# keypad-input.net
KiCad netlist of a schematic drawn in EAGLE
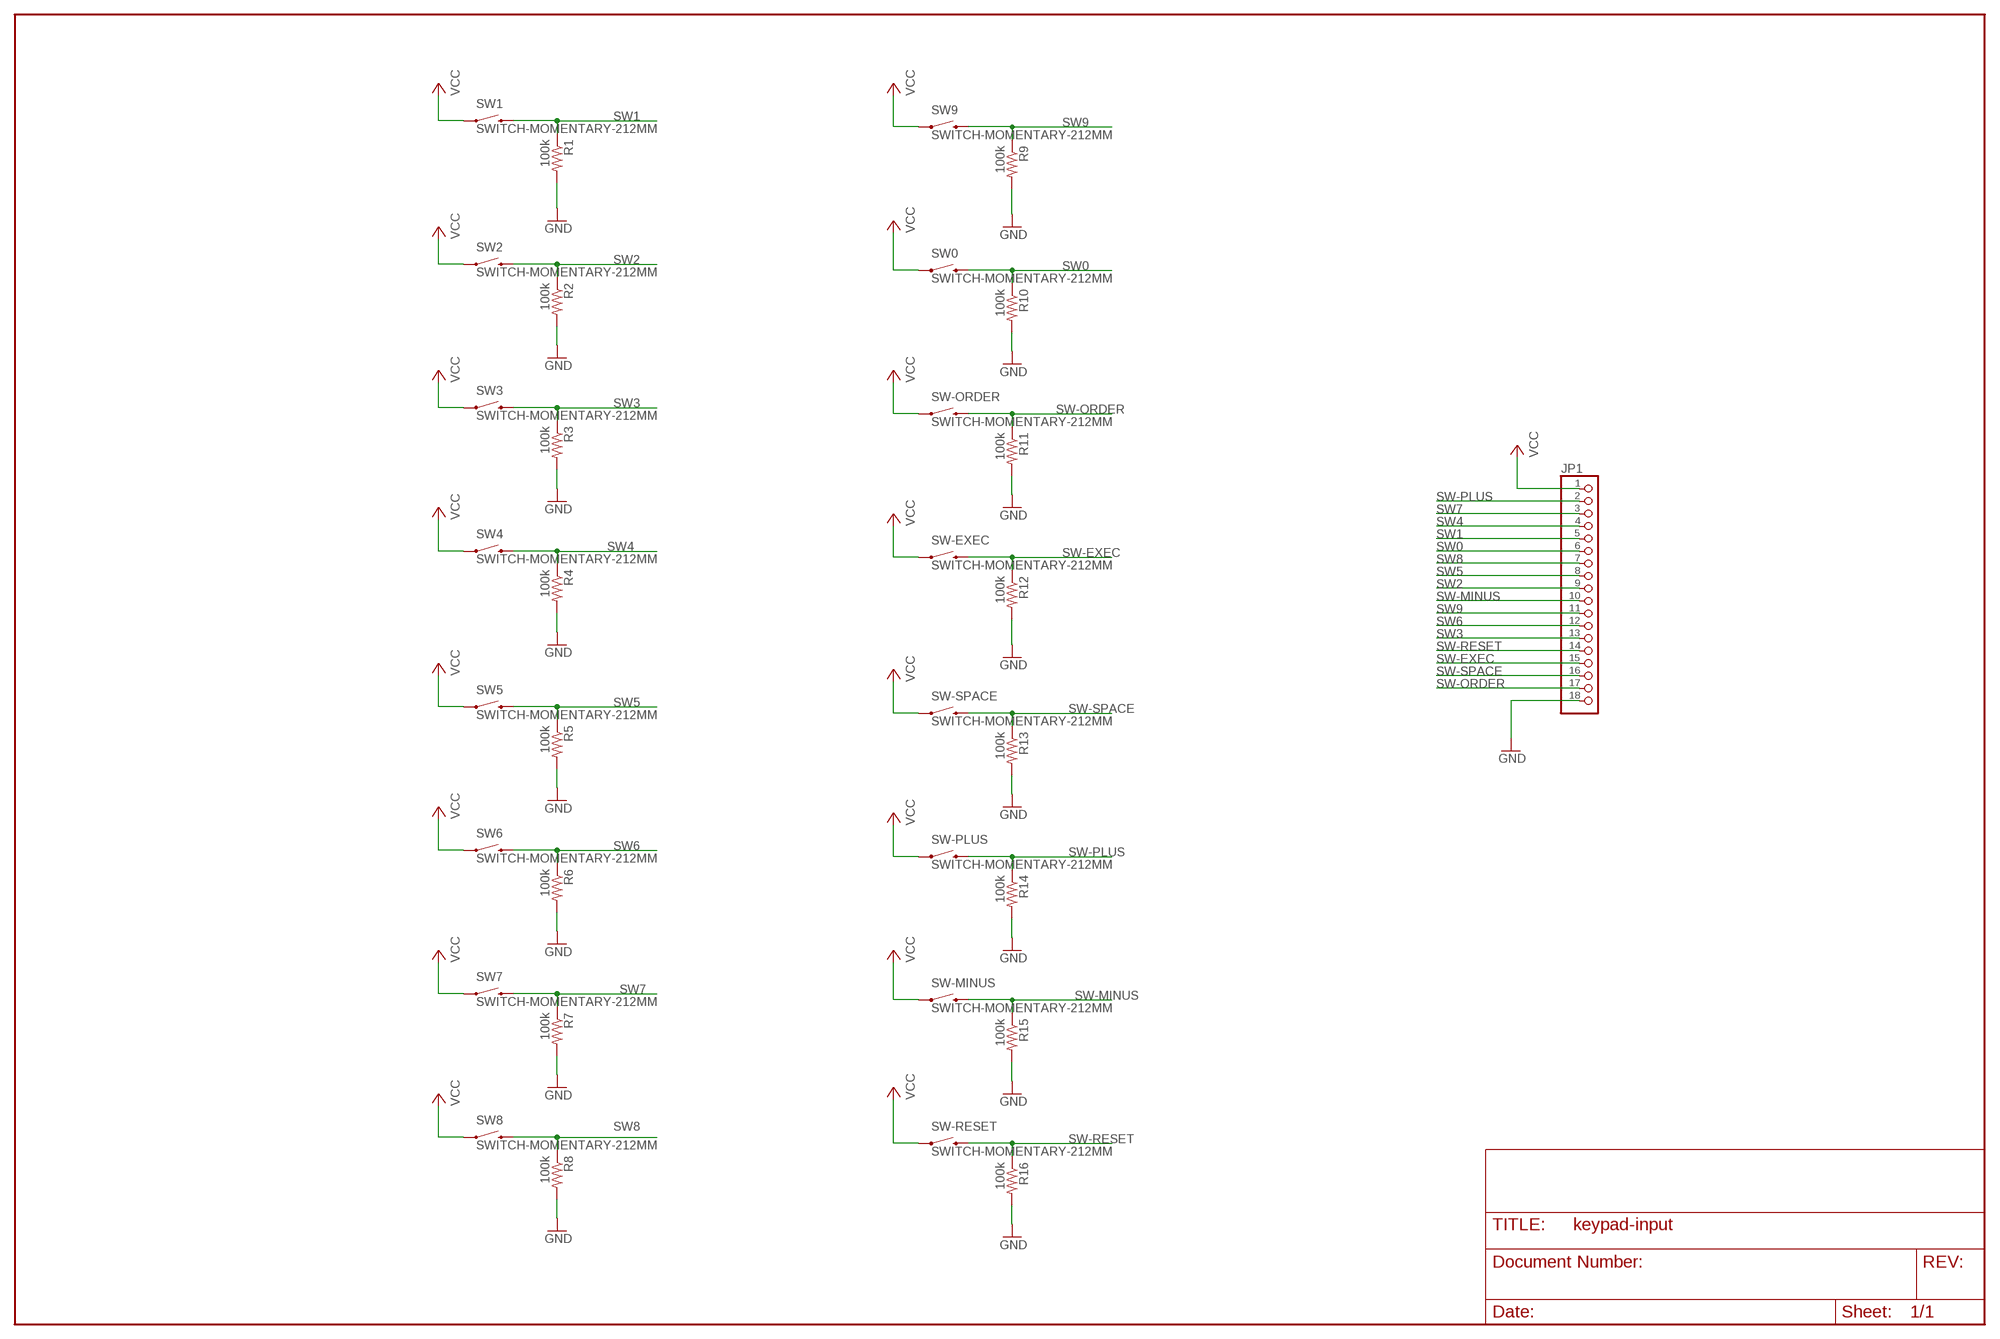
[diagram p0: schematic, sheet 1]

(export (version "E")
  (design (tool "Eeschema 10.0.6"))
  (components
    (comp (ref "JP1")
      (value "PINHD-1X18")
      (footprint "eagle-import:1X18")
      (libsource (lib "eagle-import") (part "PINHD-1X18"))
    )
    (comp (ref "R1")
      (value "100k")
      (footprint "eagle-import:R0805")
      (libsource (lib "eagle-import") (part "R-US_R0805"))
    )
    (comp (ref "R2")
      (value "100k")
      (footprint "eagle-import:R0805")
      (libsource (lib "eagle-import") (part "R-US_R0805"))
    )
    (comp (ref "R3")
      (value "100k")
      (footprint "eagle-import:R0805")
      (libsource (lib "eagle-import") (part "R-US_R0805"))
    )
    (comp (ref "R4")
      (value "100k")
      (footprint "eagle-import:R0805")
      (libsource (lib "eagle-import") (part "R-US_R0805"))
    )
    (comp (ref "R5")
      (value "100k")
      (footprint "eagle-import:R0805")
      (libsource (lib "eagle-import") (part "R-US_R0805"))
    )
    (comp (ref "R6")
      (value "100k")
      (footprint "eagle-import:R0805")
      (libsource (lib "eagle-import") (part "R-US_R0805"))
    )
    (comp (ref "R7")
      (value "100k")
      (footprint "eagle-import:R0805")
      (libsource (lib "eagle-import") (part "R-US_R0805"))
    )
    (comp (ref "R8")
      (value "100k")
      (footprint "eagle-import:R0805")
      (libsource (lib "eagle-import") (part "R-US_R0805"))
    )
    (comp (ref "R9")
      (value "100k")
      (footprint "eagle-import:R0805")
      (libsource (lib "eagle-import") (part "R-US_R0805"))
    )
    (comp (ref "R10")
      (value "100k")
      (footprint "eagle-import:R0805")
      (libsource (lib "eagle-import") (part "R-US_R0805"))
    )
    (comp (ref "R11")
      (value "100k")
      (footprint "eagle-import:R0805")
      (libsource (lib "eagle-import") (part "R-US_R0805"))
    )
    (comp (ref "R12")
      (value "100k")
      (footprint "eagle-import:R0805")
      (libsource (lib "eagle-import") (part "R-US_R0805"))
    )
    (comp (ref "R13")
      (value "100k")
      (footprint "eagle-import:R0805")
      (libsource (lib "eagle-import") (part "R-US_R0805"))
    )
    (comp (ref "R14")
      (value "100k")
      (footprint "eagle-import:R0805")
      (libsource (lib "eagle-import") (part "R-US_R0805"))
    )
    (comp (ref "R15")
      (value "100k")
      (footprint "eagle-import:R0805")
      (libsource (lib "eagle-import") (part "R-US_R0805"))
    )
    (comp (ref "R16")
      (value "100k")
      (footprint "eagle-import:R0805")
      (libsource (lib "eagle-import") (part "R-US_R0805"))
    )
    (comp (ref "SW-EXEC")
      (value "SWITCH-MOMENTARY-212MM")
      (footprint "eagle-import:TACTILE-PTH-12MM")
      (libsource (lib "eagle-import") (part "SWITCH-MOMENTARY-212MM"))
    )
    (comp (ref "SW-MINUS")
      (value "SWITCH-MOMENTARY-212MM")
      (footprint "eagle-import:TACTILE-PTH-12MM")
      (libsource (lib "eagle-import") (part "SWITCH-MOMENTARY-212MM"))
    )
    (comp (ref "SW-ORDER")
      (value "SWITCH-MOMENTARY-212MM")
      (footprint "eagle-import:TACTILE-PTH-12MM")
      (libsource (lib "eagle-import") (part "SWITCH-MOMENTARY-212MM"))
    )
    (comp (ref "SW-PLUS")
      (value "SWITCH-MOMENTARY-212MM")
      (footprint "eagle-import:TACTILE-PTH-12MM")
      (libsource (lib "eagle-import") (part "SWITCH-MOMENTARY-212MM"))
    )
    (comp (ref "SW-RESET")
      (value "SWITCH-MOMENTARY-212MM")
      (footprint "eagle-import:TACTILE-PTH-12MM")
      (libsource (lib "eagle-import") (part "SWITCH-MOMENTARY-212MM"))
    )
    (comp (ref "SW-SPACE")
      (value "SWITCH-MOMENTARY-212MM")
      (footprint "eagle-import:TACTILE-PTH-12MM")
      (libsource (lib "eagle-import") (part "SWITCH-MOMENTARY-212MM"))
    )
    (comp (ref "SW0")
      (value "SWITCH-MOMENTARY-212MM")
      (footprint "eagle-import:TACTILE-PTH-12MM")
      (libsource (lib "eagle-import") (part "SWITCH-MOMENTARY-212MM"))
    )
    (comp (ref "SW1")
      (value "SWITCH-MOMENTARY-212MM")
      (footprint "eagle-import:TACTILE-PTH-12MM")
      (libsource (lib "eagle-import") (part "SWITCH-MOMENTARY-212MM"))
    )
    (comp (ref "SW2")
      (value "SWITCH-MOMENTARY-212MM")
      (footprint "eagle-import:TACTILE-PTH-12MM")
      (libsource (lib "eagle-import") (part "SWITCH-MOMENTARY-212MM"))
    )
    (comp (ref "SW3")
      (value "SWITCH-MOMENTARY-212MM")
      (footprint "eagle-import:TACTILE-PTH-12MM")
      (libsource (lib "eagle-import") (part "SWITCH-MOMENTARY-212MM"))
    )
    (comp (ref "SW4")
      (value "SWITCH-MOMENTARY-212MM")
      (footprint "eagle-import:TACTILE-PTH-12MM")
      (libsource (lib "eagle-import") (part "SWITCH-MOMENTARY-212MM"))
    )
    (comp (ref "SW5")
      (value "SWITCH-MOMENTARY-212MM")
      (footprint "eagle-import:TACTILE-PTH-12MM")
      (libsource (lib "eagle-import") (part "SWITCH-MOMENTARY-212MM"))
    )
    (comp (ref "SW6")
      (value "SWITCH-MOMENTARY-212MM")
      (footprint "eagle-import:TACTILE-PTH-12MM")
      (libsource (lib "eagle-import") (part "SWITCH-MOMENTARY-212MM"))
    )
    (comp (ref "SW7")
      (value "SWITCH-MOMENTARY-212MM")
      (footprint "eagle-import:TACTILE-PTH-12MM")
      (libsource (lib "eagle-import") (part "SWITCH-MOMENTARY-212MM"))
    )
    (comp (ref "SW8")
      (value "SWITCH-MOMENTARY-212MM")
      (footprint "eagle-import:TACTILE-PTH-12MM")
      (libsource (lib "eagle-import") (part "SWITCH-MOMENTARY-212MM"))
    )
    (comp (ref "SW9")
      (value "SWITCH-MOMENTARY-212MM")
      (footprint "eagle-import:TACTILE-PTH-12MM")
      (libsource (lib "eagle-import") (part "SWITCH-MOMENTARY-212MM"))
    )
  )
  (nets
    (net (code "1") (name "/SW-EXEC") (class "Default")
      (node (ref "JP1") (pin "15") (pinfunction "15_15") (pintype "passive"))
      (node (ref "R12") (pin "1") (pinfunction "1_1") (pintype "passive"))
      (node (ref "SW-EXEC") (pin "3") (pinfunction "2_3") (pintype "passive"))
    )
    (net (code "2") (name "/SW-MINUS") (class "Default")
      (node (ref "JP1") (pin "10") (pinfunction "10_10") (pintype "passive"))
      (node (ref "R15") (pin "1") (pinfunction "1_1") (pintype "passive"))
      (node (ref "SW-MINUS") (pin "3") (pinfunction "2_3") (pintype "passive"))
    )
    (net (code "3") (name "/SW-ORDER") (class "Default")
      (node (ref "JP1") (pin "17") (pinfunction "17_17") (pintype "passive"))
      (node (ref "R11") (pin "1") (pinfunction "1_1") (pintype "passive"))
      (node (ref "SW-ORDER") (pin "3") (pinfunction "2_3") (pintype "passive"))
    )
    (net (code "4") (name "/SW-PLUS") (class "Default")
      (node (ref "JP1") (pin "2") (pinfunction "2_2") (pintype "passive"))
      (node (ref "R14") (pin "1") (pinfunction "1_1") (pintype "passive"))
      (node (ref "SW-PLUS") (pin "3") (pinfunction "2_3") (pintype "passive"))
    )
    (net (code "5") (name "/SW-RESET") (class "Default")
      (node (ref "JP1") (pin "14") (pinfunction "14_14") (pintype "passive"))
      (node (ref "R16") (pin "1") (pinfunction "1_1") (pintype "passive"))
      (node (ref "SW-RESET") (pin "3") (pinfunction "2_3") (pintype "passive"))
    )
    (net (code "6") (name "/SW-SPACE") (class "Default")
      (node (ref "JP1") (pin "16") (pinfunction "16_16") (pintype "passive"))
      (node (ref "R13") (pin "1") (pinfunction "1_1") (pintype "passive"))
      (node (ref "SW-SPACE") (pin "3") (pinfunction "2_3") (pintype "passive"))
    )
    (net (code "7") (name "/SW0") (class "Default")
      (node (ref "JP1") (pin "6") (pinfunction "6_6") (pintype "passive"))
      (node (ref "R10") (pin "1") (pinfunction "1_1") (pintype "passive"))
      (node (ref "SW0") (pin "3") (pinfunction "2_3") (pintype "passive"))
    )
    (net (code "8") (name "/SW1") (class "Default")
      (node (ref "JP1") (pin "5") (pinfunction "5_5") (pintype "passive"))
      (node (ref "R1") (pin "1") (pinfunction "1_1") (pintype "passive"))
      (node (ref "SW1") (pin "3") (pinfunction "2_3") (pintype "passive"))
    )
    (net (code "9") (name "/SW2") (class "Default")
      (node (ref "JP1") (pin "9") (pinfunction "9_9") (pintype "passive"))
      (node (ref "R2") (pin "1") (pinfunction "1_1") (pintype "passive"))
      (node (ref "SW2") (pin "3") (pinfunction "2_3") (pintype "passive"))
    )
    (net (code "10") (name "/SW3") (class "Default")
      (node (ref "JP1") (pin "13") (pinfunction "13_13") (pintype "passive"))
      (node (ref "R3") (pin "1") (pinfunction "1_1") (pintype "passive"))
      (node (ref "SW3") (pin "3") (pinfunction "2_3") (pintype "passive"))
    )
    (net (code "11") (name "/SW4") (class "Default")
      (node (ref "JP1") (pin "4") (pinfunction "4_4") (pintype "passive"))
      (node (ref "R4") (pin "1") (pinfunction "1_1") (pintype "passive"))
      (node (ref "SW4") (pin "3") (pinfunction "2_3") (pintype "passive"))
    )
    (net (code "12") (name "/SW5") (class "Default")
      (node (ref "JP1") (pin "8") (pinfunction "8_8") (pintype "passive"))
      (node (ref "R5") (pin "1") (pinfunction "1_1") (pintype "passive"))
      (node (ref "SW5") (pin "3") (pinfunction "2_3") (pintype "passive"))
    )
    (net (code "13") (name "/SW6") (class "Default")
      (node (ref "JP1") (pin "12") (pinfunction "12_12") (pintype "passive"))
      (node (ref "R6") (pin "1") (pinfunction "1_1") (pintype "passive"))
      (node (ref "SW6") (pin "3") (pinfunction "2_3") (pintype "passive"))
    )
    (net (code "14") (name "/SW7") (class "Default")
      (node (ref "JP1") (pin "3") (pinfunction "3_3") (pintype "passive"))
      (node (ref "R7") (pin "1") (pinfunction "1_1") (pintype "passive"))
      (node (ref "SW7") (pin "3") (pinfunction "2_3") (pintype "passive"))
    )
    (net (code "15") (name "/SW8") (class "Default")
      (node (ref "JP1") (pin "7") (pinfunction "7_7") (pintype "passive"))
      (node (ref "R8") (pin "1") (pinfunction "1_1") (pintype "passive"))
      (node (ref "SW8") (pin "3") (pinfunction "2_3") (pintype "passive"))
    )
    (net (code "16") (name "/SW9") (class "Default")
      (node (ref "JP1") (pin "11") (pinfunction "11_11") (pintype "passive"))
      (node (ref "R9") (pin "1") (pinfunction "1_1") (pintype "passive"))
      (node (ref "SW9") (pin "3") (pinfunction "2_3") (pintype "passive"))
    )
    (net (code "17") (name "GND") (class "Default")
      (node (ref "JP1") (pin "18") (pinfunction "18_18") (pintype "passive"))
      (node (ref "R1") (pin "2") (pinfunction "2_2") (pintype "passive"))
      (node (ref "R10") (pin "2") (pinfunction "2_2") (pintype "passive"))
      (node (ref "R11") (pin "2") (pinfunction "2_2") (pintype "passive"))
      (node (ref "R12") (pin "2") (pinfunction "2_2") (pintype "passive"))
      (node (ref "R13") (pin "2") (pinfunction "2_2") (pintype "passive"))
      (node (ref "R14") (pin "2") (pinfunction "2_2") (pintype "passive"))
      (node (ref "R15") (pin "2") (pinfunction "2_2") (pintype "passive"))
      (node (ref "R16") (pin "2") (pinfunction "2_2") (pintype "passive"))
      (node (ref "R2") (pin "2") (pinfunction "2_2") (pintype "passive"))
      (node (ref "R3") (pin "2") (pinfunction "2_2") (pintype "passive"))
      (node (ref "R4") (pin "2") (pinfunction "2_2") (pintype "passive"))
      (node (ref "R5") (pin "2") (pinfunction "2_2") (pintype "passive"))
      (node (ref "R6") (pin "2") (pinfunction "2_2") (pintype "passive"))
      (node (ref "R7") (pin "2") (pinfunction "2_2") (pintype "passive"))
      (node (ref "R8") (pin "2") (pinfunction "2_2") (pintype "passive"))
      (node (ref "R9") (pin "2") (pinfunction "2_2") (pintype "passive"))
    )
    (net (code "18") (name "VCC") (class "Default")
      (node (ref "JP1") (pin "1") (pinfunction "1_1") (pintype "passive"))
      (node (ref "SW-EXEC") (pin "1") (pinfunction "1_1") (pintype "passive"))
      (node (ref "SW-MINUS") (pin "1") (pinfunction "1_1") (pintype "passive"))
      (node (ref "SW-ORDER") (pin "1") (pinfunction "1_1") (pintype "passive"))
      (node (ref "SW-PLUS") (pin "1") (pinfunction "1_1") (pintype "passive"))
      (node (ref "SW-RESET") (pin "1") (pinfunction "1_1") (pintype "passive"))
      (node (ref "SW-SPACE") (pin "1") (pinfunction "1_1") (pintype "passive"))
      (node (ref "SW0") (pin "1") (pinfunction "1_1") (pintype "passive"))
      (node (ref "SW1") (pin "1") (pinfunction "1_1") (pintype "passive"))
      (node (ref "SW2") (pin "1") (pinfunction "1_1") (pintype "passive"))
      (node (ref "SW3") (pin "1") (pinfunction "1_1") (pintype "passive"))
      (node (ref "SW4") (pin "1") (pinfunction "1_1") (pintype "passive"))
      (node (ref "SW5") (pin "1") (pinfunction "1_1") (pintype "passive"))
      (node (ref "SW6") (pin "1") (pinfunction "1_1") (pintype "passive"))
      (node (ref "SW7") (pin "1") (pinfunction "1_1") (pintype "passive"))
      (node (ref "SW8") (pin "1") (pinfunction "1_1") (pintype "passive"))
      (node (ref "SW9") (pin "1") (pinfunction "1_1") (pintype "passive"))
    )
  )
)
